# cpu.net
KiCad netlist of a schematic drawn in Altium Designer
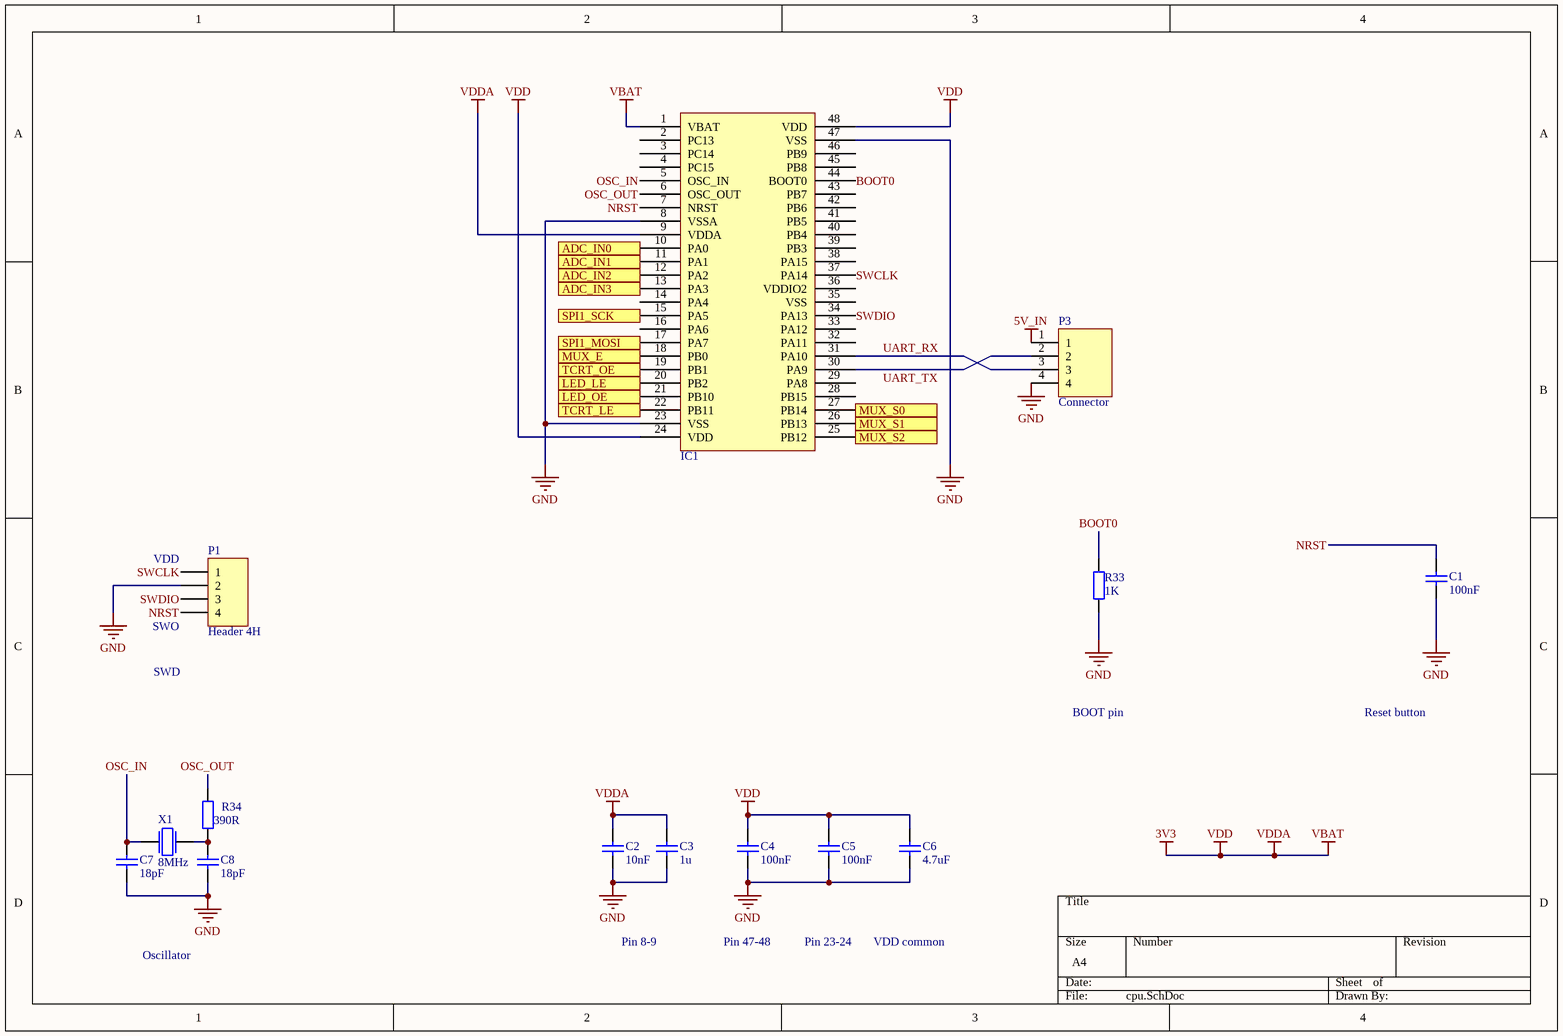
[diagram p0: cpu.SchDoc]

(export (version "E")
  (design (tool "Eeschema 10.0.6"))
  (components
    (comp (ref "C1")
      (value "100nF")
      (footprint "FP_0805_CAP_085")
      (description "Capacitor")
      (fields (field (name "VOLTAGE") "50V"))
      (libsource (lib "hallglib-2018") (part "CAP 100nF"))
    )
    (comp (ref "C2")
      (value "10nF")
      (footprint "FP_0805_CAP_085")
      (description "Capacitor")
      (libsource (lib "hallglib-2018") (part "CAP 10nF"))
    )
    (comp (ref "C3")
      (value "1u")
      (footprint "FP_0805_CAP_085")
      (description "Capacitor")
      (libsource (lib "hallglib") (part "CAP"))
    )
    (comp (ref "C4")
      (value "100nF")
      (footprint "FP_0805_CAP_085")
      (description "Capacitor")
      (fields (field (name "VOLTAGE") "50V"))
      (libsource (lib "hallglib-2018") (part "CAP 100nF"))
    )
    (comp (ref "C5")
      (value "100nF")
      (footprint "FP_0805_CAP_085")
      (description "Capacitor")
      (fields (field (name "VOLTAGE") "50V"))
      (libsource (lib "hallglib-2018") (part "CAP 100nF"))
    )
    (comp (ref "C6")
      (value "4.7uF")
      (footprint "FP_0805_CAP_085")
      (description "Capacitor")
      (libsource (lib "hallglib-2018") (part "CAP 47uF"))
    )
    (comp (ref "C7")
      (value "18pF")
      (footprint "FP_0805_CAP_085")
      (description "Capacitor")
      (libsource (lib "hallglib") (part "CAP"))
    )
    (comp (ref "C8")
      (value "18pF")
      (footprint "FP_0805_CAP_085")
      (description "Capacitor")
      (libsource (lib "hallglib") (part "CAP"))
    )
    (comp (ref "IC1")
      (value "STM32F030C8T6")
      (footprint "LQFP48")
      (description "STM32F030C8T6 ARM MCU")
      (libsource (lib "mb") (part "STM32F030C8T6"))
    )
    (comp (ref "P1")
      (value "Header 4H")
      (footprint "HDR1X4H")
      (description "Header, 4-Pin, Right Angle")
      (fields (field (name "PUBLISHER") "Altium Limited"))
      (libsource (lib "Miscellaneous Connectors") (part "Header 4H"))
    )
    (comp (ref "P3")
      (value "Connector")
      (footprint "FP_CONN4_TAP_254MM_90")
      (description "4pin Connector")
      (libsource (lib "hallglib") (part "Connector_4pin"))
    )
    (comp (ref "R33")
      (value "1K")
      (footprint "FP_0805_RES")
      (description "Resistor")
      (libsource (lib "hallglib") (part "RES"))
    )
    (comp (ref "R34")
      (value "390R")
      (footprint "FP_0805_RES")
      (description "Resistor")
      (libsource (lib "hallglib-2018") (part "RES 390R"))
    )
    (comp (ref "X1")
      (value "8MHz")
      (footprint "FP_CRYSTAL_HC49")
      (description "Quarz Crystal")
      (libsource (lib "hallglib-2018") (part "Crystal"))
    )
  )
  (nets
    (net (code "1") (name "/ADC_IN0") (class "Default")
      (node (ref "IC1") (pin "10") (pinfunction "PA0_10") (pintype "passive"))
    )
    (net (code "2") (name "/ADC_IN1") (class "Default")
      (node (ref "IC1") (pin "11") (pinfunction "PA1_11") (pintype "passive"))
    )
    (net (code "3") (name "/ADC_IN2") (class "Default")
      (node (ref "IC1") (pin "12") (pinfunction "PA2_12") (pintype "passive"))
    )
    (net (code "4") (name "/ADC_IN3") (class "Default")
      (node (ref "IC1") (pin "13") (pinfunction "PA3_13") (pintype "passive"))
    )
    (net (code "5") (name "/BOOT0") (class "Default")
      (node (ref "IC1") (pin "44") (pinfunction "BOOT0_44") (pintype "passive"))
      (node (ref "R33") (pin "2") (pinfunction "2_2") (pintype "passive"))
    )
    (net (code "6") (name "/LED_LE") (class "Default")
      (node (ref "IC1") (pin "20") (pinfunction "PB2_20") (pintype "passive"))
    )
    (net (code "7") (name "/LED_OE") (class "Default")
      (node (ref "IC1") (pin "21") (pinfunction "PB10_21") (pintype "passive"))
    )
    (net (code "8") (name "/MUX_E") (class "Default")
      (node (ref "IC1") (pin "18") (pinfunction "PB0_18") (pintype "passive"))
    )
    (net (code "9") (name "/MUX_S0") (class "Default")
      (node (ref "IC1") (pin "27") (pinfunction "PB14_27") (pintype "passive"))
    )
    (net (code "10") (name "/MUX_S1") (class "Default")
      (node (ref "IC1") (pin "26") (pinfunction "PB13_26") (pintype "passive"))
    )
    (net (code "11") (name "/MUX_S2") (class "Default")
      (node (ref "IC1") (pin "25") (pinfunction "PB12_25") (pintype "passive"))
    )
    (net (code "12") (name "/NRST") (class "Default")
      (node (ref "C1") (pin "2") (pinfunction "2_2") (pintype "passive"))
      (node (ref "IC1") (pin "7") (pinfunction "NRST_7") (pintype "passive"))
      (node (ref "P1") (pin "4") (pinfunction "4_4") (pintype "passive"))
    )
    (net (code "13") (name "/OSC_IN") (class "Default")
      (node (ref "C7") (pin "2") (pinfunction "2_2") (pintype "passive"))
      (node (ref "IC1") (pin "5") (pinfunction "OSC_IN_5") (pintype "passive"))
      (node (ref "X1") (pin "1") (pinfunction "1_1") (pintype "passive"))
    )
    (net (code "14") (name "/OSC_OUT") (class "Default")
      (node (ref "IC1") (pin "6") (pinfunction "OSC_OUT_6") (pintype "passive"))
      (node (ref "R34") (pin "2") (pinfunction "2_2") (pintype "passive"))
    )
    (net (code "15") (name "/SPI1_MOSI") (class "Default")
      (node (ref "IC1") (pin "17") (pinfunction "PA7_17") (pintype "passive"))
    )
    (net (code "16") (name "/SPI1_SCK") (class "Default")
      (node (ref "IC1") (pin "15") (pinfunction "PA5_15") (pintype "passive"))
    )
    (net (code "17") (name "/SWCLK") (class "Default")
      (node (ref "IC1") (pin "37") (pinfunction "PA14_37") (pintype "passive"))
      (node (ref "P1") (pin "1") (pinfunction "1_1") (pintype "passive"))
    )
    (net (code "18") (name "/SWDIO") (class "Default")
      (node (ref "IC1") (pin "34") (pinfunction "PA13_34") (pintype "passive"))
      (node (ref "P1") (pin "3") (pinfunction "3_3") (pintype "passive"))
    )
    (net (code "19") (name "/TCRT_LE") (class "Default")
      (node (ref "IC1") (pin "22") (pinfunction "PB11_22") (pintype "passive"))
    )
    (net (code "20") (name "/TCRT_OE") (class "Default")
      (node (ref "IC1") (pin "19") (pinfunction "PB1_19") (pintype "passive"))
    )
    (net (code "21") (name "/UART_RX") (class "Default")
      (node (ref "IC1") (pin "31") (pinfunction "PA10_31") (pintype "passive"))
      (node (ref "P3") (pin "3") (pinfunction "3_3") (pintype "passive"))
    )
    (net (code "22") (name "/UART_TX") (class "Default")
      (node (ref "IC1") (pin "30") (pinfunction "PA9_30") (pintype "passive"))
      (node (ref "P3") (pin "2") (pinfunction "2_2") (pintype "passive"))
    )
    (net (code "23") (name "3V3") (class "Default")
      (node (ref "C2") (pin "2") (pinfunction "2_2") (pintype "passive"))
      (node (ref "C3") (pin "2") (pinfunction "2_2") (pintype "passive"))
      (node (ref "C4") (pin "2") (pinfunction "2_2") (pintype "passive"))
      (node (ref "C5") (pin "2") (pinfunction "2_2") (pintype "passive"))
      (node (ref "C6") (pin "2") (pinfunction "2_2") (pintype "passive"))
      (node (ref "IC1") (pin "1") (pinfunction "VBAT_1") (pintype "passive"))
      (node (ref "IC1") (pin "24") (pinfunction "VDD_24") (pintype "passive"))
      (node (ref "IC1") (pin "48") (pinfunction "VDD_48") (pintype "passive"))
      (node (ref "IC1") (pin "9") (pinfunction "VDDA_9") (pintype "passive"))
    )
    (net (code "24") (name "5V_IN") (class "Default")
      (node (ref "P3") (pin "1") (pinfunction "1_1") (pintype "passive"))
    )
    (net (code "25") (name "GND") (class "Default")
      (node (ref "C1") (pin "1") (pinfunction "1_1") (pintype "passive"))
      (node (ref "C2") (pin "1") (pinfunction "1_1") (pintype "passive"))
      (node (ref "C3") (pin "1") (pinfunction "1_1") (pintype "passive"))
      (node (ref "C4") (pin "1") (pinfunction "1_1") (pintype "passive"))
      (node (ref "C5") (pin "1") (pinfunction "1_1") (pintype "passive"))
      (node (ref "C6") (pin "1") (pinfunction "1_1") (pintype "passive"))
      (node (ref "C7") (pin "1") (pinfunction "1_1") (pintype "passive"))
      (node (ref "C8") (pin "1") (pinfunction "1_1") (pintype "passive"))
      (node (ref "IC1") (pin "23") (pinfunction "VSS_23") (pintype "passive"))
      (node (ref "IC1") (pin "47") (pinfunction "VSS_47") (pintype "passive"))
      (node (ref "IC1") (pin "8") (pinfunction "VSSA_8") (pintype "passive"))
      (node (ref "P1") (pin "2") (pinfunction "2_2") (pintype "passive"))
      (node (ref "P3") (pin "4") (pinfunction "4_4") (pintype "passive"))
      (node (ref "R33") (pin "1") (pinfunction "1_1") (pintype "passive"))
    )
    (net (code "26") (name "Net-(C8-Pad2)") (class "Default")
      (node (ref "C8") (pin "2") (pinfunction "2_2") (pintype "passive"))
      (node (ref "R34") (pin "1") (pinfunction "1_1") (pintype "passive"))
      (node (ref "X1") (pin "2") (pinfunction "2_2") (pintype "passive"))
    )
    (net (code "27") (name "unconnected-(IC1-PA4-Pad14)") (class "Default")
      (node (ref "IC1") (pin "14") (pinfunction "PA4_14") (pintype "passive"))
    )
    (net (code "28") (name "unconnected-(IC1-PA6-Pad16)") (class "Default")
      (node (ref "IC1") (pin "16") (pinfunction "PA6_16") (pintype "passive"))
    )
    (net (code "29") (name "unconnected-(IC1-PA8-Pad29)") (class "Default")
      (node (ref "IC1") (pin "29") (pinfunction "PA8_29") (pintype "passive"))
    )
    (net (code "30") (name "unconnected-(IC1-PA11-Pad32)") (class "Default")
      (node (ref "IC1") (pin "32") (pinfunction "PA11_32") (pintype "passive"))
    )
    (net (code "31") (name "unconnected-(IC1-PA12-Pad33)") (class "Default")
      (node (ref "IC1") (pin "33") (pinfunction "PA12_33") (pintype "passive"))
    )
    (net (code "32") (name "unconnected-(IC1-PA15-Pad38)") (class "Default")
      (node (ref "IC1") (pin "38") (pinfunction "PA15_38") (pintype "passive"))
    )
    (net (code "33") (name "unconnected-(IC1-PB3-Pad39)") (class "Default")
      (node (ref "IC1") (pin "39") (pinfunction "PB3_39") (pintype "passive"))
    )
    (net (code "34") (name "unconnected-(IC1-PB4-Pad40)") (class "Default")
      (node (ref "IC1") (pin "40") (pinfunction "PB4_40") (pintype "passive"))
    )
    (net (code "35") (name "unconnected-(IC1-PB5-Pad41)") (class "Default")
      (node (ref "IC1") (pin "41") (pinfunction "PB5_41") (pintype "passive"))
    )
    (net (code "36") (name "unconnected-(IC1-PB6-Pad42)") (class "Default")
      (node (ref "IC1") (pin "42") (pinfunction "PB6_42") (pintype "passive"))
    )
    (net (code "37") (name "unconnected-(IC1-PB7-Pad43)") (class "Default")
      (node (ref "IC1") (pin "43") (pinfunction "PB7_43") (pintype "passive"))
    )
    (net (code "38") (name "unconnected-(IC1-PB8-Pad45)") (class "Default")
      (node (ref "IC1") (pin "45") (pinfunction "PB8_45") (pintype "passive"))
    )
    (net (code "39") (name "unconnected-(IC1-PB9-Pad46)") (class "Default")
      (node (ref "IC1") (pin "46") (pinfunction "PB9_46") (pintype "passive"))
    )
    (net (code "40") (name "unconnected-(IC1-PB15-Pad28)") (class "Default")
      (node (ref "IC1") (pin "28") (pinfunction "PB15_28") (pintype "passive"))
    )
    (net (code "41") (name "unconnected-(IC1-PC13-Pad2)") (class "Default")
      (node (ref "IC1") (pin "2") (pinfunction "PC13_2") (pintype "passive"))
    )
    (net (code "42") (name "unconnected-(IC1-PC14-Pad3)") (class "Default")
      (node (ref "IC1") (pin "3") (pinfunction "PC14_3") (pintype "passive"))
    )
    (net (code "43") (name "unconnected-(IC1-PC15-Pad4)") (class "Default")
      (node (ref "IC1") (pin "4") (pinfunction "PC15_4") (pintype "passive"))
    )
    (net (code "44") (name "unconnected-(IC1-VDDIO2-Pad36)") (class "Default")
      (node (ref "IC1") (pin "36") (pinfunction "VDDIO2_36") (pintype "passive"))
    )
    (net (code "45") (name "unconnected-(IC1-VSS-Pad35)") (class "Default")
      (node (ref "IC1") (pin "35") (pinfunction "VSS_35") (pintype "passive"))
    )
  )
)
